# 7_can_rc_i2c_analog.net
KiCad netlist of a schematic drawn in Altium Designer
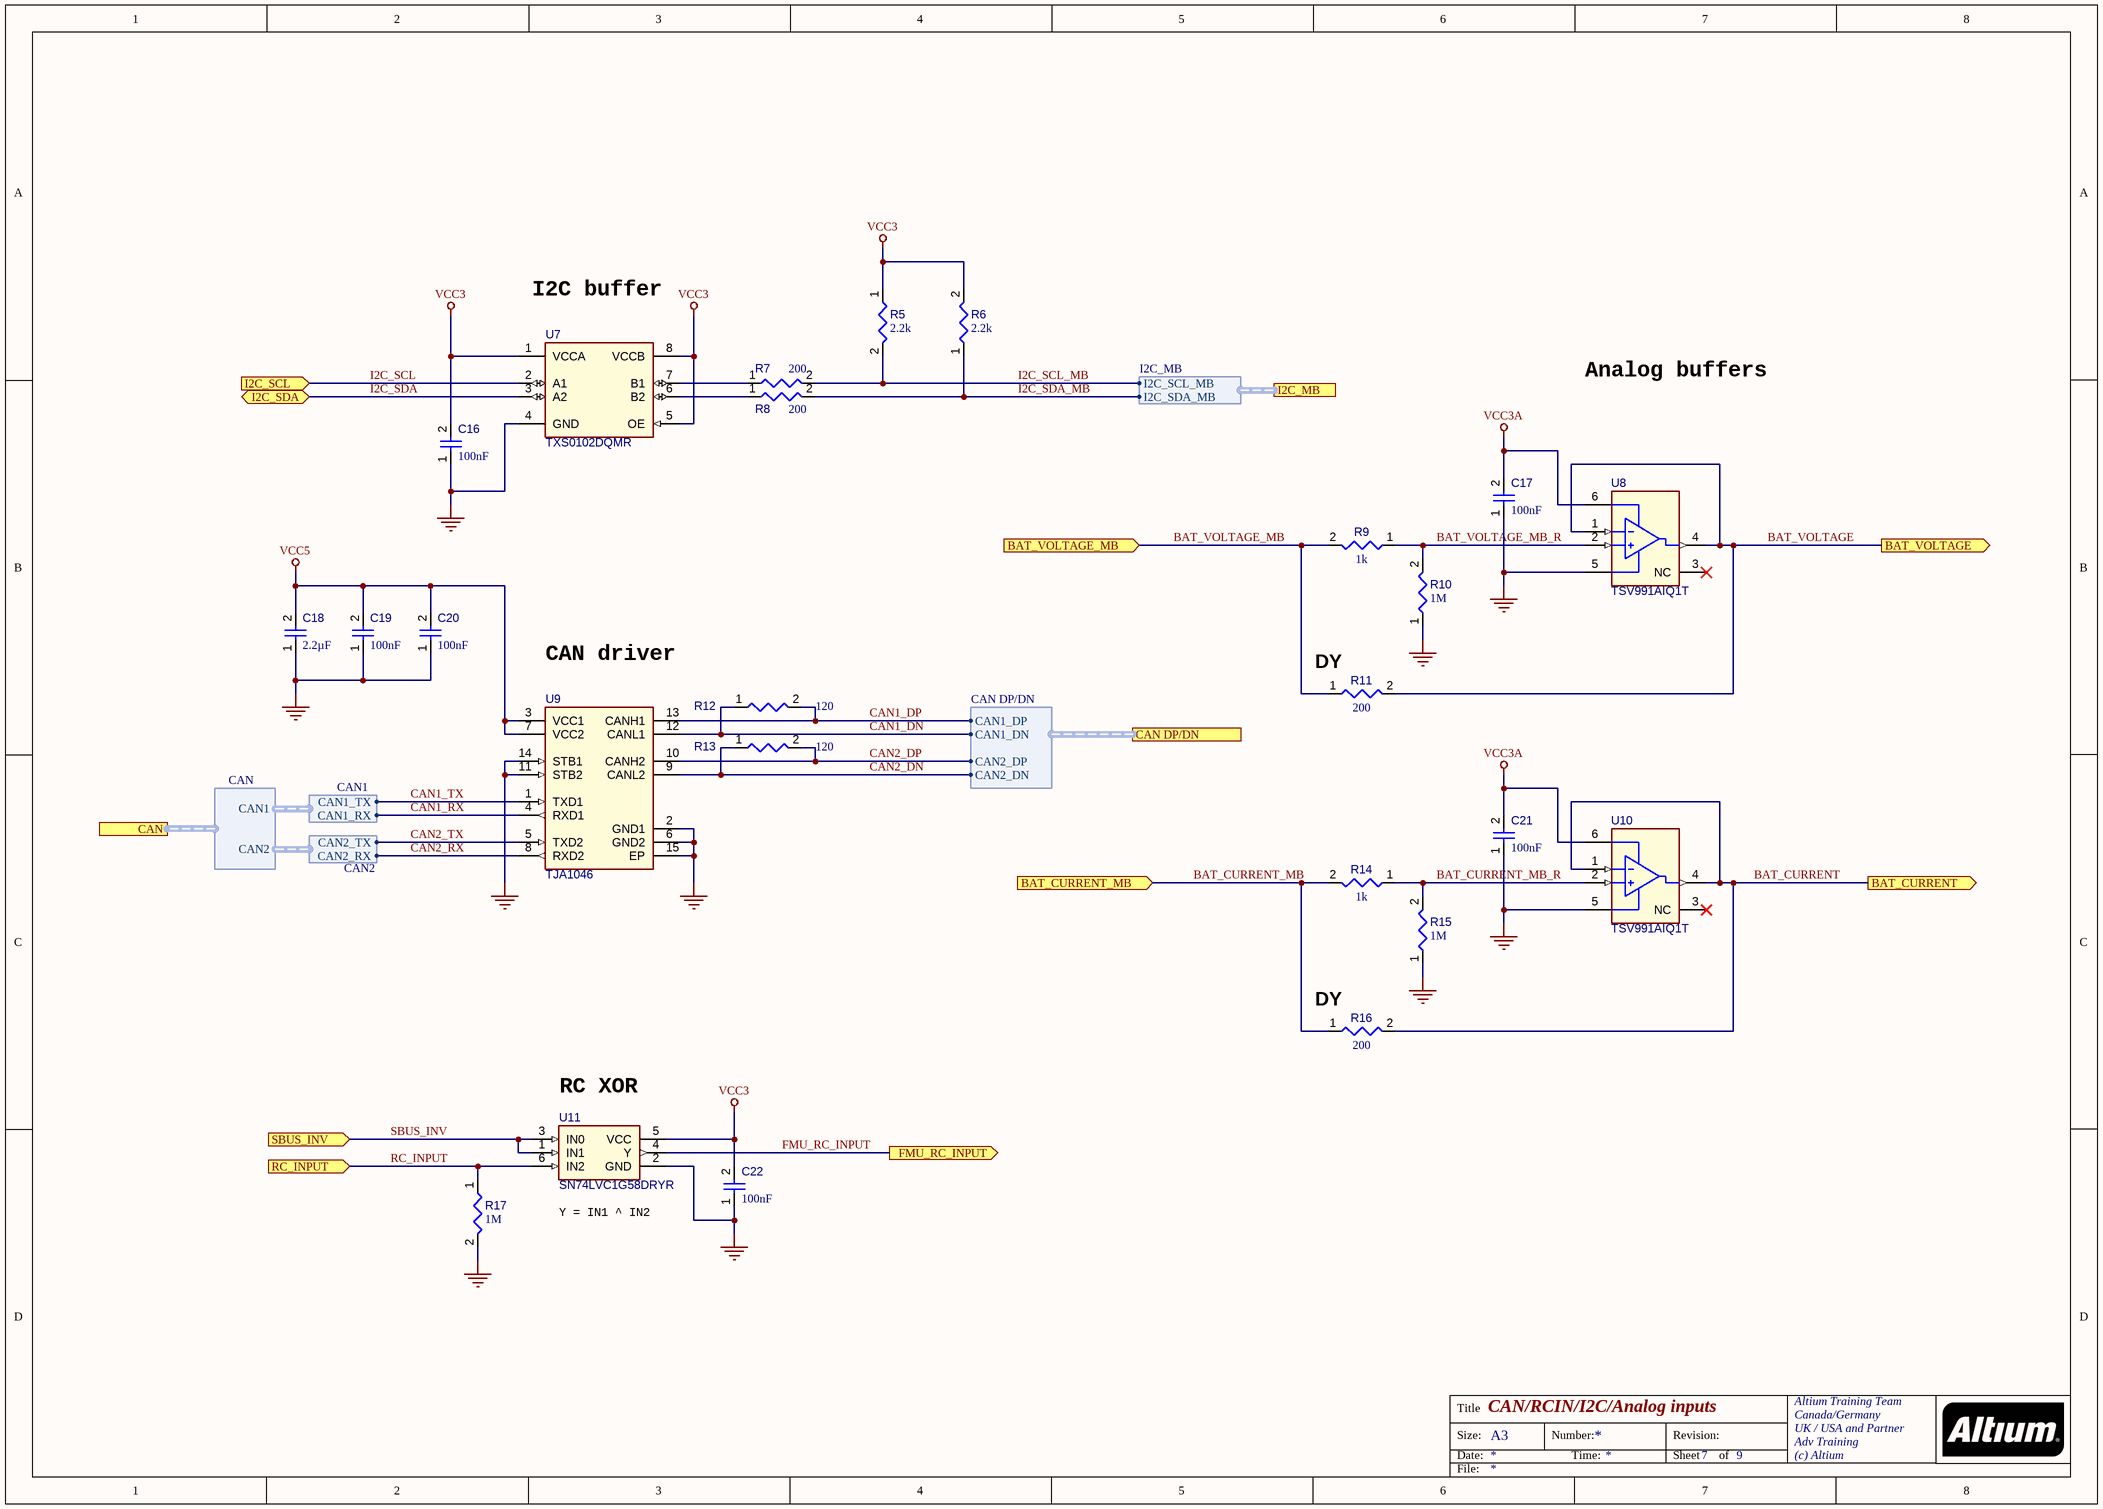
[diagram p0:  7_can_rc_i2c_analog.SchDoc]

(export (version "E")
  (design (tool "Eeschema 10.0.6"))
  (components
    (comp (ref "C16")
      (value "100nF")
      (footprint "CAPC0402(1005)60_L")
      (description "Chip Capacitor, 100nF +/-20%, 10V, 0402, Thickness 0.6 mm")
      (fields (field (name "TOLERANCE") "20%") (field (name "Comment") "Capacitor 100nF +/-20% 10V 0402"))
      (libsource (lib "MHH -  Altium Advanced Course A365 01") (part "CAP-NP-2"))
    )
    (comp (ref "C17")
      (value "100nF")
      (footprint "CAPC0402(1005)60_L")
      (description "Chip Capacitor, 100nF +/-20%, 10V, 0402, Thickness 0.6 mm")
      (fields (field (name "TOLERANCE") "20%") (field (name "Comment") "Capacitor 100nF +/-20% 10V 0402"))
      (libsource (lib "MHH -  Altium Advanced Course A365 01") (part "CAP-NP-2"))
    )
    (comp (ref "C18")
      (value "2.2µF")
      (footprint "CAPC0402(1005)60_L")
      (description "Chip Capacitor, 2,2µF +/-20%, 10V, 0402, Thickness 0.6 mm")
      (fields (field (name "TOLERANCE") "10%") (field (name "Comment") "Capacitor 2,2µF +/-20% 10V 0402"))
      (libsource (lib "MHH -  Altium Advanced Course A365 01") (part "CAP-NP-2"))
    )
    (comp (ref "C19")
      (value "100nF")
      (footprint "CAPC0402(1005)60_L")
      (description "Chip Capacitor, 100nF +/-20%, 10V, 0402, Thickness 0.6 mm")
      (fields (field (name "TOLERANCE") "20%") (field (name "Comment") "Capacitor 100nF +/-20% 10V 0402"))
      (libsource (lib "MHH -  Altium Advanced Course A365 01") (part "CAP-NP-2"))
    )
    (comp (ref "C20")
      (value "100nF")
      (footprint "CAPC0402(1005)60_L")
      (description "Chip Capacitor, 100nF +/-20%, 10V, 0402, Thickness 0.6 mm")
      (fields (field (name "TOLERANCE") "20%") (field (name "Comment") "Capacitor 100nF +/-20% 10V 0402"))
      (libsource (lib "MHH -  Altium Advanced Course A365 01") (part "CAP-NP-2"))
    )
    (comp (ref "C21")
      (value "100nF")
      (footprint "CAPC0402(1005)60_L")
      (description "Chip Capacitor, 100nF +/-20%, 10V, 0402, Thickness 0.6 mm")
      (fields (field (name "TOLERANCE") "20%") (field (name "Comment") "Capacitor 100nF +/-20% 10V 0402"))
      (libsource (lib "MHH -  Altium Advanced Course A365 01") (part "CAP-NP-2"))
    )
    (comp (ref "C22")
      (value "100nF")
      (footprint "CAPC0402(1005)60_L")
      (description "Chip Capacitor, 100nF +/-20%, 10V, 0402, Thickness 0.6 mm")
      (fields (field (name "TOLERANCE") "20%") (field (name "Comment") "Capacitor 100nF +/-20% 10V 0402"))
      (libsource (lib "MHH -  Altium Advanced Course A365 01") (part "CAP-NP-2"))
    )
    (comp (ref "R5")
      (value "2.2k")
      (footprint "RESC0402(1005)_L")
      (description "Chip Resistor, 2,2 kOhms, +/-5 %, 63 mW, -55 to 155 degC, 0402")
      (fields (field (name "POWER") "63mW") (field (name "TOLERANCE") "5%"))
      (libsource (lib "MHH -  Altium Advanced Course A365 01") (part "RES-2"))
    )
    (comp (ref "R6")
      (value "2.2k")
      (footprint "RESC0402(1005)_L")
      (description "Chip Resistor, 2,2 kOhms, +/-5 %, 63 mW, -55 to 155 degC, 0402")
      (fields (field (name "POWER") "63mW") (field (name "TOLERANCE") "5%"))
      (libsource (lib "MHH -  Altium Advanced Course A365 01") (part "RES-2"))
    )
    (comp (ref "R7")
      (value "200")
      (footprint "RESC0402(1005)_L")
      (description "Chip Resistor, 200 Ohms, +/-5 %, 63 mW, -55 to 155 degC, 0402")
      (fields (field (name "POWER") "63mW") (field (name "TOLERANCE") "5%"))
      (libsource (lib "MHH -  Altium Advanced Course A365 01") (part "RES-2"))
    )
    (comp (ref "R8")
      (value "200")
      (footprint "RESC0402(1005)_L")
      (description "Chip Resistor, 200 Ohms, +/-5 %, 63 mW, -55 to 155 degC, 0402")
      (fields (field (name "POWER") "63mW") (field (name "TOLERANCE") "5%"))
      (libsource (lib "MHH -  Altium Advanced Course A365 01") (part "RES-2"))
    )
    (comp (ref "R9")
      (value "1k")
      (footprint "RESC0402(1005)_L")
      (description "Chip Resistor, 1 kOhms, +/-5 %, 63 mW, -55 to 155 degC, 0402")
      (fields (field (name "TOLERANCE") "5%") (field (name "POWER") "63mW"))
      (libsource (lib "MHH -  Altium Advanced Course A365 01") (part "RES-2"))
    )
    (comp (ref "R10")
      (value "1M")
      (footprint "RESC0402(1005)_L")
      (description "Chip Resistor, 1 MOhms, +/-5 %, 63 mW, -55 to 155 degC, 0402")
      (fields (field (name "TOLERANCE") "5%") (field (name "POWER") "63mW"))
      (libsource (lib "MHH -  Altium Advanced Course A365 01") (part "RES-2"))
    )
    (comp (ref "R11")
      (value "200")
      (footprint "RESC0402(1005)_L")
      (description "Chip Resistor, 200 Ohms, +/-5 %, 63 mW, -55 to 155 degC, 0402")
      (fields (field (name "POWER") "63mW") (field (name "TOLERANCE") "5%"))
      (libsource (lib "MHH -  Altium Advanced Course A365 01") (part "RES-2"))
    )
    (comp (ref "R12")
      (value "120")
      (footprint "RESC0603(1608)_L")
      (description "Chip Resistor, 120 Ohms, +/-5 %, 0.1 W, -55 to 155 degC, 0603")
      (fields (field (name "TOLERANCE") "5%") (field (name "POWER") "100mW"))
      (libsource (lib "MHH -  Altium Advanced Course A365 01") (part "RES-2"))
    )
    (comp (ref "R13")
      (value "120")
      (footprint "RESC0603(1608)_L")
      (description "Chip Resistor, 120 Ohms, +/-5 %, 0.1 W, -55 to 155 degC, 0603")
      (fields (field (name "TOLERANCE") "5%") (field (name "POWER") "100mW"))
      (libsource (lib "MHH -  Altium Advanced Course A365 01") (part "RES-2"))
    )
    (comp (ref "R14")
      (value "1k")
      (footprint "RESC0402(1005)_L")
      (description "Chip Resistor, 1 kOhms, +/-5 %, 63 mW, -55 to 155 degC, 0402")
      (fields (field (name "TOLERANCE") "5%") (field (name "POWER") "63mW"))
      (libsource (lib "MHH -  Altium Advanced Course A365 01") (part "RES-2"))
    )
    (comp (ref "R15")
      (value "1M")
      (footprint "RESC0402(1005)_L")
      (description "Chip Resistor, 1 MOhms, +/-5 %, 63 mW, -55 to 155 degC, 0402")
      (fields (field (name "TOLERANCE") "5%") (field (name "POWER") "63mW"))
      (libsource (lib "MHH -  Altium Advanced Course A365 01") (part "RES-2"))
    )
    (comp (ref "R16")
      (value "200")
      (footprint "RESC0402(1005)_L")
      (description "Chip Resistor, 200 Ohms, +/-5 %, 63 mW, -55 to 155 degC, 0402")
      (fields (field (name "POWER") "63mW") (field (name "TOLERANCE") "5%"))
      (libsource (lib "MHH -  Altium Advanced Course A365 01") (part "RES-2"))
    )
    (comp (ref "R17")
      (value "1M")
      (footprint "RESC0402(1005)_L")
      (description "Chip Resistor, 1 MOhms, +/-5 %, 63 mW, -55 to 155 degC, 0402")
      (fields (field (name "TOLERANCE") "5%") (field (name "POWER") "63mW"))
      (libsource (lib "MHH -  Altium Advanced Course A365 01") (part "RES-2"))
    )
    (comp (ref "U7")
      (value "TXS0102DQMR")
      (footprint "DQM")
      (description "IC TRANSLATOR VOLTAGE 8-X2SON")
      (libsource (lib "MHH -  Altium Advanced Course A365 01") (part "CMP-001-0022-1"))
    )
    (comp (ref "U8")
      (value "TSV991AIQ1T")
      (footprint "STM-DFN-8_V")
      (libsource (lib "MHH -  Altium Advanced Course A365 01") (part "CMP-001-0008-5"))
    )
    (comp (ref "U9")
      (value "TJA1046")
      (footprint "NXP-SOT1086-2_L")
      (libsource (lib "MHH -  Altium Advanced Course A365 01") (part "CMP-00180-5"))
    )
    (comp (ref "U10")
      (value "TSV991AIQ1T")
      (footprint "STM-DFN-8_V")
      (libsource (lib "MHH -  Altium Advanced Course A365 01") (part "CMP-001-0008-5"))
    )
    (comp (ref "U11")
      (value "SN74LVC1G58DRYR")
      (footprint "DRY0006A_V")
      (description "CONFIGURABLE MULTIPLE-FUNCTION GATE, DRY0006A, LARGE T&R")
      (libsource (lib "MHH -  Altium Advanced Course A365 01") (part "CMP-00132-5"))
    )
  )
  (nets
    (net (code "7") (name "/BAT_CURRENT") (class "Default")
      (node (ref "R16") (pin "2") (pinfunction "2_2") (pintype "passive"))
      (node (ref "U10") (pin "1") (pinfunction "IN-_1") (pintype "input"))
      (node (ref "U10") (pin "4") (pinfunction "OUT_4") (pintype "output"))
    )
    (net (code "8") (name "/BAT_CURRENT_MB") (class "Default")
      (node (ref "R14") (pin "2") (pinfunction "2_2") (pintype "passive"))
      (node (ref "R16") (pin "1") (pinfunction "1_1") (pintype "passive"))
    )
    (net (code "9") (name "/BAT_CURRENT_MB_R") (class "Default")
      (node (ref "R14") (pin "1") (pinfunction "1_1") (pintype "passive"))
      (node (ref "R15") (pin "2") (pinfunction "2_2") (pintype "passive"))
      (node (ref "U10") (pin "2") (pinfunction "IN+_2") (pintype "input"))
    )
    (net (code "10") (name "/BAT_VOLTAGE") (class "Default")
      (node (ref "R11") (pin "2") (pinfunction "2_2") (pintype "passive"))
      (node (ref "U8") (pin "1") (pinfunction "IN-_1") (pintype "input"))
      (node (ref "U8") (pin "4") (pinfunction "OUT_4") (pintype "output"))
    )
    (net (code "11") (name "/BAT_VOLTAGE_MB") (class "Default")
      (node (ref "R11") (pin "1") (pinfunction "1_1") (pintype "passive"))
      (node (ref "R9") (pin "2") (pinfunction "2_2") (pintype "passive"))
    )
    (net (code "12") (name "/BAT_VOLTAGE_MB_R") (class "Default")
      (node (ref "R10") (pin "2") (pinfunction "2_2") (pintype "passive"))
      (node (ref "R9") (pin "1") (pinfunction "1_1") (pintype "passive"))
      (node (ref "U8") (pin "2") (pinfunction "IN+_2") (pintype "input"))
    )
    (net (code "13") (name "/CAN1_DN") (class "Default")
      (node (ref "R12") (pin "1") (pinfunction "1_1") (pintype "passive"))
      (node (ref "U9") (pin "12") (pinfunction "CANL1_12") (pintype "passive"))
    )
    (net (code "14") (name "/CAN1_DP") (class "Default")
      (node (ref "R12") (pin "2") (pinfunction "2_2") (pintype "passive"))
      (node (ref "U9") (pin "13") (pinfunction "CANH1_13") (pintype "passive"))
    )
    (net (code "15") (name "/CAN1_RX") (class "Default")
      (node (ref "U9") (pin "4") (pinfunction "RXD1_4") (pintype "output"))
    )
    (net (code "16") (name "/CAN1_TX") (class "Default")
      (node (ref "U9") (pin "1") (pinfunction "TXD1_1") (pintype "input"))
    )
    (net (code "17") (name "/CAN2_DN") (class "Default")
      (node (ref "R13") (pin "1") (pinfunction "1_1") (pintype "passive"))
      (node (ref "U9") (pin "9") (pinfunction "CANL2_9") (pintype "passive"))
    )
    (net (code "18") (name "/CAN2_DP") (class "Default")
      (node (ref "R13") (pin "2") (pinfunction "2_2") (pintype "passive"))
      (node (ref "U9") (pin "10") (pinfunction "CANH2_10") (pintype "passive"))
    )
    (net (code "19") (name "/CAN2_RX") (class "Default")
      (node (ref "U9") (pin "8") (pinfunction "RXD2_8") (pintype "output"))
    )
    (net (code "20") (name "/CAN2_TX") (class "Default")
      (node (ref "U9") (pin "5") (pinfunction "TXD2_5") (pintype "input"))
    )
    (net (code "22") (name "/FMU_RC_INPUT") (class "Default")
      (node (ref "U11") (pin "4") (pinfunction "Y_4") (pintype "output"))
    )
    (net (code "23") (name "/I2C_SCL") (class "Default")
      (node (ref "U7") (pin "2") (pinfunction "A1_2") (pintype "bidirectional"))
    )
    (net (code "24") (name "/I2C_SCL_MB") (class "Default")
      (node (ref "R5") (pin "2") (pinfunction "2_2") (pintype "passive"))
      (node (ref "R7") (pin "2") (pinfunction "2_2") (pintype "passive"))
    )
    (net (code "25") (name "/I2C_SDA") (class "Default")
      (node (ref "U7") (pin "3") (pinfunction "A2_3") (pintype "bidirectional"))
    )
    (net (code "26") (name "/I2C_SDA_MB") (class "Default")
      (node (ref "R6") (pin "1") (pinfunction "1_1") (pintype "passive"))
      (node (ref "R8") (pin "2") (pinfunction "2_2") (pintype "passive"))
    )
    (net (code "27") (name "/RC_INPUT") (class "Default")
      (node (ref "R17") (pin "1") (pinfunction "1_1") (pintype "passive"))
      (node (ref "U11") (pin "6") (pinfunction "IN2_6") (pintype "input"))
    )
    (net (code "28") (name "/SBUS_INV") (class "Default")
      (node (ref "U11") (pin "1") (pinfunction "IN1_1") (pintype "input"))
      (node (ref "U11") (pin "3") (pinfunction "IN0_3") (pintype "input"))
    )
    (net (code "33") (name "GND") (class "Default")
      (node (ref "C16") (pin "1") (pinfunction "1_1") (pintype "passive"))
      (node (ref "C17") (pin "1") (pinfunction "1_1") (pintype "passive"))
      (node (ref "C18") (pin "1") (pinfunction "1_1") (pintype "passive"))
      (node (ref "C19") (pin "1") (pinfunction "1_1") (pintype "passive"))
      (node (ref "C20") (pin "1") (pinfunction "1_1") (pintype "passive"))
      (node (ref "C21") (pin "1") (pinfunction "1_1") (pintype "passive"))
      (node (ref "C22") (pin "1") (pinfunction "1_1") (pintype "passive"))
      (node (ref "R10") (pin "1") (pinfunction "1_1") (pintype "passive"))
      (node (ref "R15") (pin "1") (pinfunction "1_1") (pintype "passive"))
      (node (ref "R17") (pin "2") (pinfunction "2_2") (pintype "passive"))
      (node (ref "U10") (pin "5") (pinfunction "VCC-_5") (pintype "power_in"))
      (node (ref "U11") (pin "2") (pinfunction "GND_2") (pintype "power_in"))
      (node (ref "U7") (pin "4") (pinfunction "GND_4") (pintype "power_in"))
      (node (ref "U8") (pin "5") (pinfunction "VCC-_5") (pintype "power_in"))
      (node (ref "U9") (pin "11") (pinfunction "STB2_11") (pintype "input"))
      (node (ref "U9") (pin "14") (pinfunction "STB1_14") (pintype "input"))
      (node (ref "U9") (pin "15") (pinfunction "EP_15") (pintype "power_in"))
      (node (ref "U9") (pin "2") (pinfunction "GND1_2") (pintype "power_in"))
      (node (ref "U9") (pin "6") (pinfunction "GND2_6") (pintype "power_in"))
    )
    (net (code "34") (name "Net-(U7-B1)") (class "Default")
      (node (ref "R7") (pin "1") (pinfunction "1_1") (pintype "passive"))
      (node (ref "U7") (pin "7") (pinfunction "B1_7") (pintype "bidirectional"))
    )
    (net (code "35") (name "Net-(U7-B2)") (class "Default")
      (node (ref "R8") (pin "1") (pinfunction "1_1") (pintype "passive"))
      (node (ref "U7") (pin "6") (pinfunction "B2_6") (pintype "bidirectional"))
    )
    (net (code "36") (name "VCC3") (class "Default")
      (node (ref "C16") (pin "2") (pinfunction "2_2") (pintype "passive"))
      (node (ref "C22") (pin "2") (pinfunction "2_2") (pintype "passive"))
      (node (ref "R5") (pin "1") (pinfunction "1_1") (pintype "passive"))
      (node (ref "R6") (pin "2") (pinfunction "2_2") (pintype "passive"))
      (node (ref "U11") (pin "5") (pinfunction "VCC_5") (pintype "power_in"))
      (node (ref "U7") (pin "1") (pinfunction "VCCA_1") (pintype "power_in"))
      (node (ref "U7") (pin "5") (pinfunction "OE_5") (pintype "input"))
      (node (ref "U7") (pin "8") (pinfunction "VCCB_8") (pintype "power_in"))
    )
    (net (code "37") (name "VCC3A") (class "Default")
      (node (ref "C17") (pin "2") (pinfunction "2_2") (pintype "passive"))
      (node (ref "C21") (pin "2") (pinfunction "2_2") (pintype "passive"))
      (node (ref "U10") (pin "6") (pinfunction "VCC+_6") (pintype "power_in"))
      (node (ref "U8") (pin "6") (pinfunction "VCC+_6") (pintype "power_in"))
    )
    (net (code "38") (name "VCC5") (class "Default")
      (node (ref "C18") (pin "2") (pinfunction "2_2") (pintype "passive"))
      (node (ref "C19") (pin "2") (pinfunction "2_2") (pintype "passive"))
      (node (ref "C20") (pin "2") (pinfunction "2_2") (pintype "passive"))
      (node (ref "U9") (pin "3") (pinfunction "VCC1_3") (pintype "power_in"))
      (node (ref "U9") (pin "7") (pinfunction "VCC2_7") (pintype "power_in"))
    )
    (net (code "39") (name "unconnected-(U8-NC-Pad3)") (class "Default")
      (node (ref "U8") (pin "3") (pinfunction "NC_3") (pintype "passive+no_connect"))
    )
    (net (code "40") (name "unconnected-(U10-NC-Pad3)") (class "Default")
      (node (ref "U10") (pin "3") (pinfunction "NC_3") (pintype "passive+no_connect"))
    )
  )
)
